# PCB_CREATING.net
KiCad netlist of a schematic drawn in EasyEDA
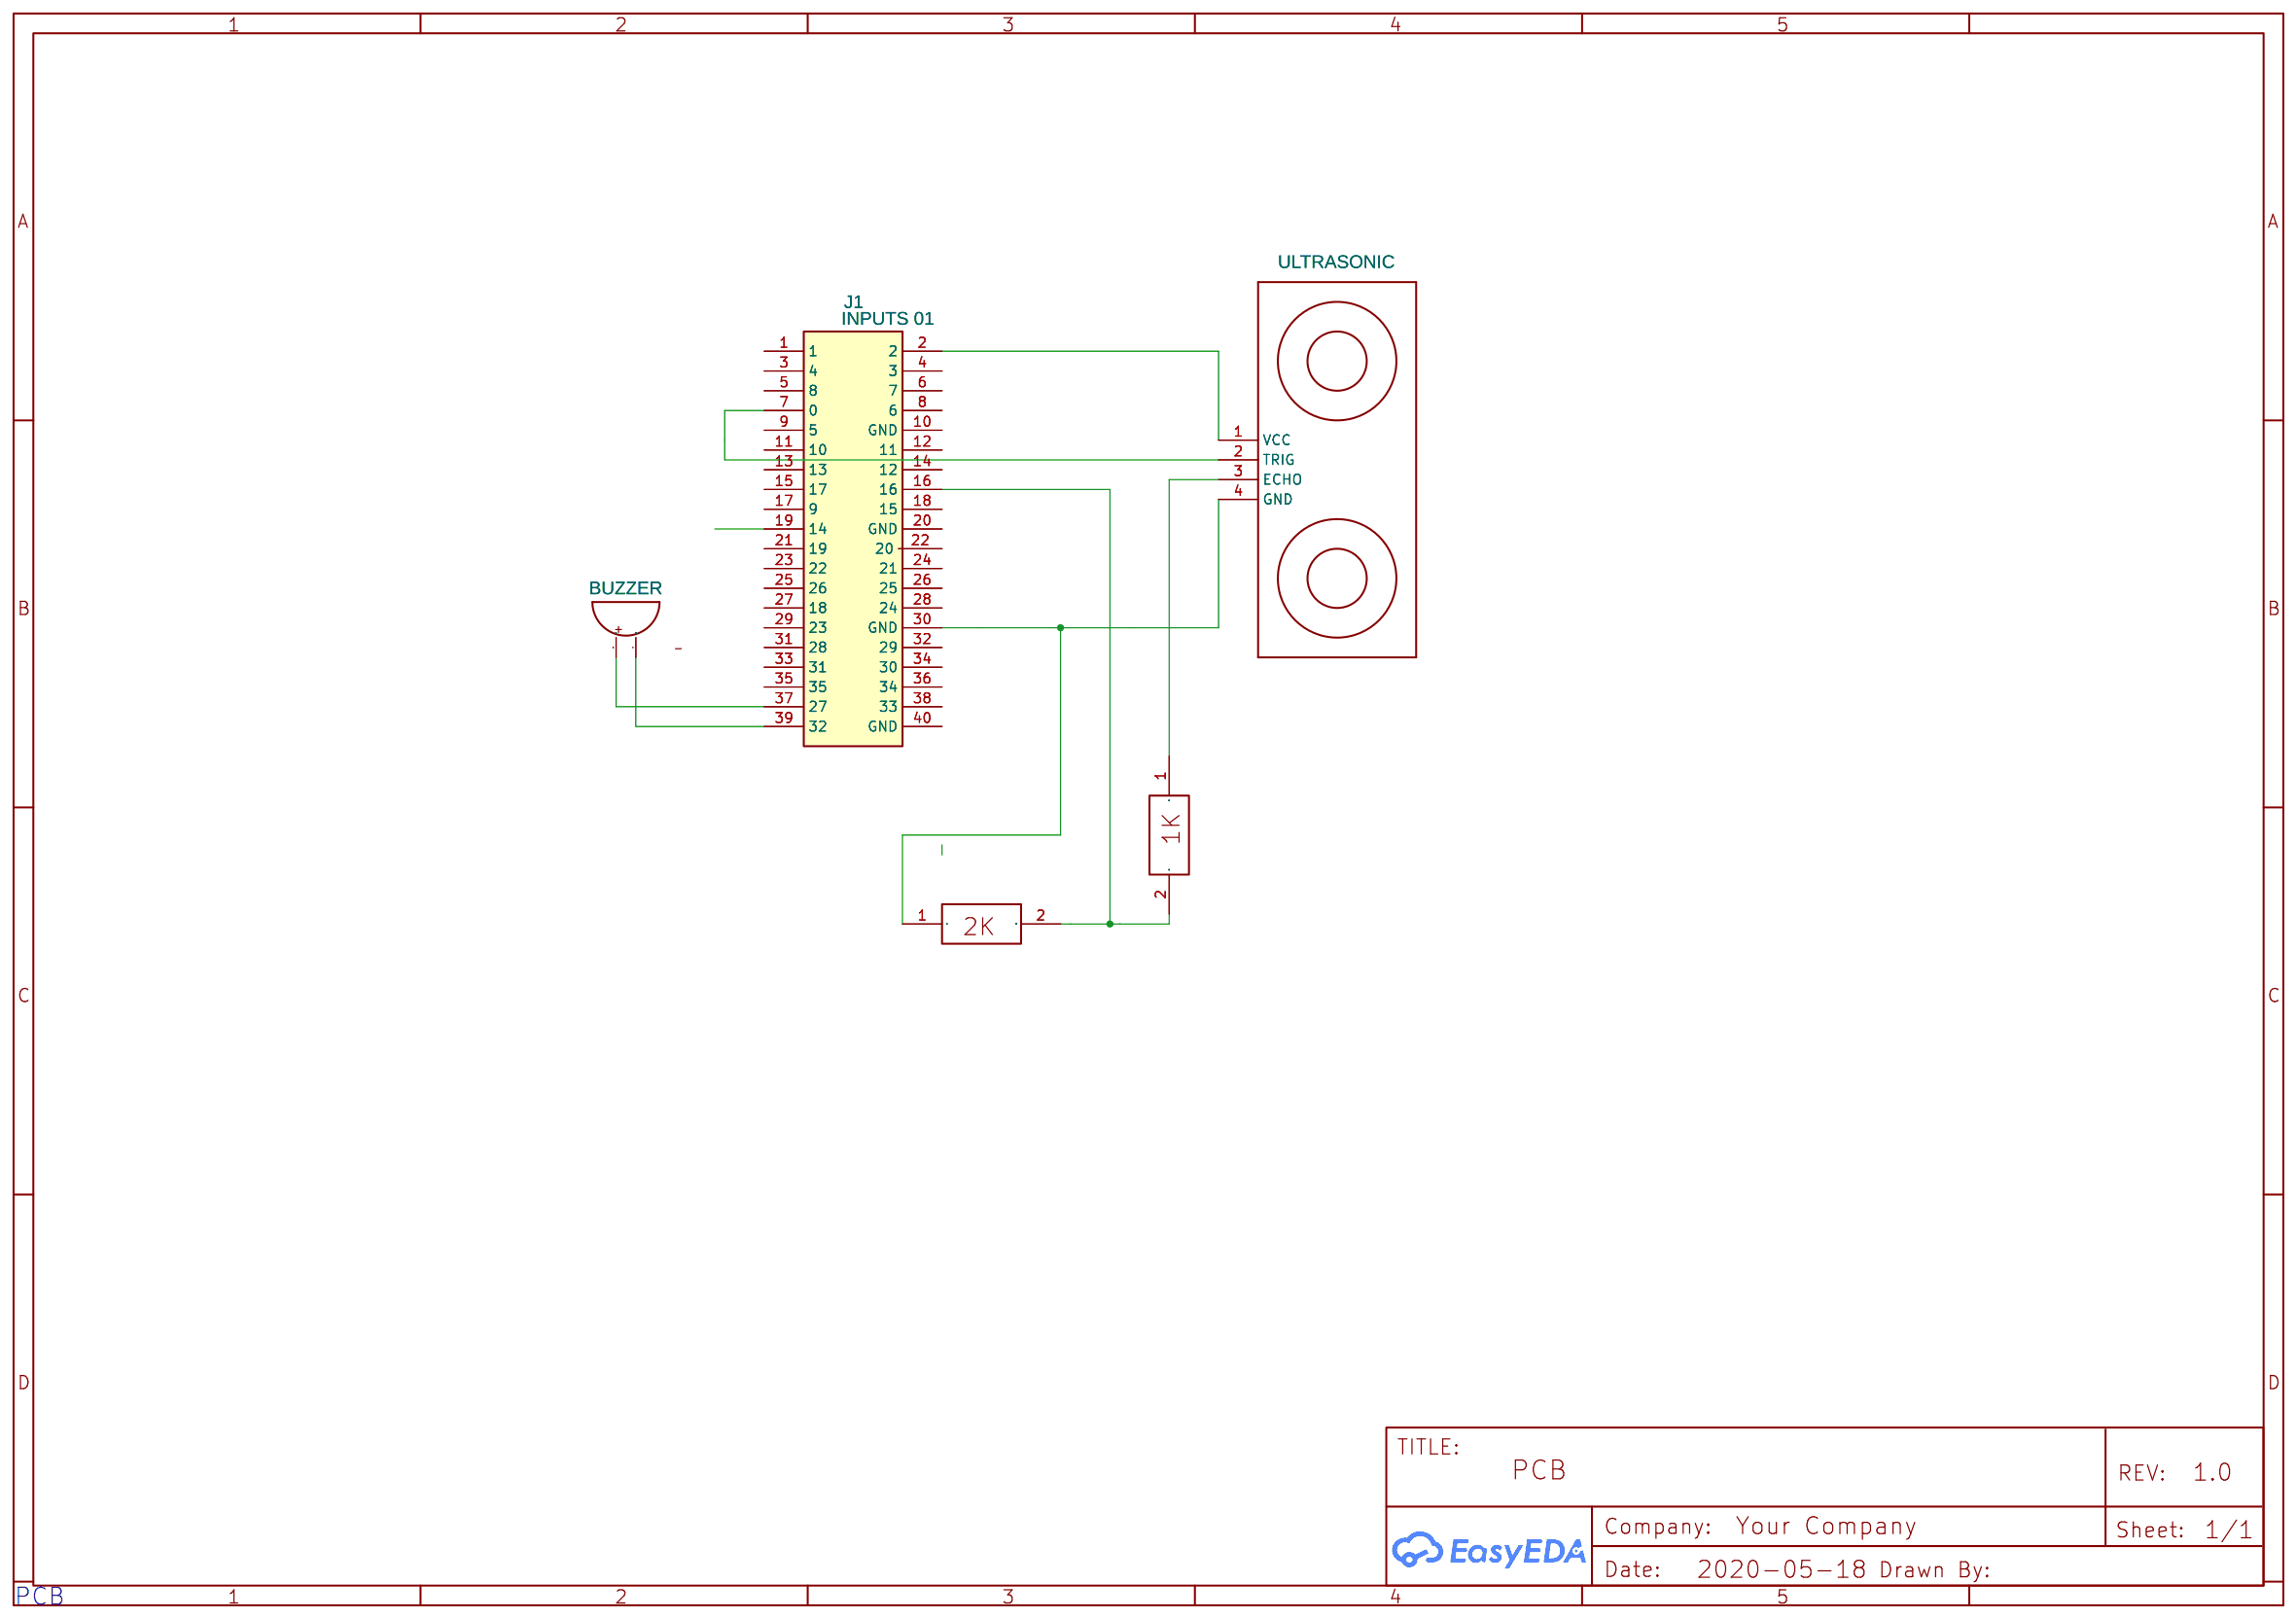
[diagram p0: schematic sheet]

(export (version "E")
  (design (tool "Eeschema 10.0.6"))
  (components
    (comp (ref "J1")
      (value "INPUTS 01")
      (fields
        (field (name "BOM_Manufacturer Part") "Header-Female-2.54_2x20")
        (field (name "BOM_Supplier Part") "C30420")
      )
      (libsource (lib "") (part "INPUTS 01"))
    )
    (comp (ref "R1") (value "1K resistor") (libsource (lib "") (part "1K resistor_1")))
    (comp (ref "R2") (value "1K resistor") (libsource (lib "") (part "1K resistor")))
    (comp (ref "SG1") (value "BUZZER") (libsource (lib "") (part "BUZZER")))
    (comp (ref "U1") (value "ULTRASONIC") (libsource (lib "") (part "ULTRASONIC")))
  )
  (nets
    (net (code "1") (name "Net-(J1-0)") (class "Default")
      (node (ref "J1") (pin "7") (pinfunction "0_7") (pintype "input"))
      (node (ref "U1") (pin "2") (pinfunction "TRIG_2") (pintype "input"))
    )
    (net (code "2") (name "Net-(J1-27)") (class "Default")
      (node (ref "J1") (pin "37") (pinfunction "27_37") (pintype "input"))
      (node (ref "SG1") (pin "+") (pinfunction "1_+") (pintype "unspecified"))
    )
    (net (code "3") (name "Net-(J1-32)") (class "Default")
      (node (ref "J1") (pin "39") (pinfunction "32_39") (pintype "input"))
      (node (ref "SG1") (pin "-") (pinfunction "2_-") (pintype "unspecified"))
    )
    (net (code "4") (name "Net-(J1-Pad16)") (class "Default")
      (node (ref "J1") (pin "16") (pinfunction "16_16") (pintype "input"))
      (node (ref "R1") (pin "2") (pinfunction "2_2") (pintype "unspecified"))
      (node (ref "R2") (pin "2") (pinfunction "2_2") (pintype "unspecified"))
    )
    (net (code "5") (name "Net-(U1-ECHO)") (class "Default")
      (node (ref "R1") (pin "1") (pinfunction "1_1") (pintype "unspecified"))
      (node (ref "U1") (pin "3") (pinfunction "ECHO_3") (pintype "output"))
    )
    (net (code "6") (name "Net-(U1-GND)") (class "Default")
      (node (ref "J1") (pin "30") (pinfunction "GND_30") (pintype "input"))
      (node (ref "R2") (pin "1") (pinfunction "1_1") (pintype "unspecified"))
      (node (ref "U1") (pin "4") (pinfunction "GND_4") (pintype "passive"))
    )
    (net (code "7") (name "Net-(U1-VCC)") (class "Default")
      (node (ref "J1") (pin "2") (pinfunction "2_2") (pintype "input"))
      (node (ref "U1") (pin "1") (pinfunction "VCC_1") (pintype "passive"))
    )
    (net (code "8") (name "unconnected-(J1-3-Pad4)") (class "Default")
      (node (ref "J1") (pin "4") (pinfunction "3_4") (pintype "input"))
    )
    (net (code "9") (name "unconnected-(J1-4-Pad3)") (class "Default")
      (node (ref "J1") (pin "3") (pinfunction "4_3") (pintype "input"))
    )
    (net (code "10") (name "unconnected-(J1-5-Pad9)") (class "Default")
      (node (ref "J1") (pin "9") (pinfunction "5_9") (pintype "input"))
    )
    (net (code "11") (name "unconnected-(J1-6-Pad8)") (class "Default")
      (node (ref "J1") (pin "8") (pinfunction "6_8") (pintype "input"))
    )
    (net (code "12") (name "unconnected-(J1-7-Pad6)") (class "Default")
      (node (ref "J1") (pin "6") (pinfunction "7_6") (pintype "input"))
    )
    (net (code "13") (name "unconnected-(J1-8-Pad5)") (class "Default")
      (node (ref "J1") (pin "5") (pinfunction "8_5") (pintype "input"))
    )
    (net (code "14") (name "unconnected-(J1-9-Pad17)") (class "Default")
      (node (ref "J1") (pin "17") (pinfunction "9_17") (pintype "input"))
    )
    (net (code "15") (name "unconnected-(J1-10-Pad11)") (class "Default")
      (node (ref "J1") (pin "11") (pinfunction "10_11") (pintype "input"))
    )
    (net (code "16") (name "unconnected-(J1-11-Pad12)") (class "Default")
      (node (ref "J1") (pin "12") (pinfunction "11_12") (pintype "input"))
    )
    (net (code "17") (name "unconnected-(J1-12-Pad14)") (class "Default")
      (node (ref "J1") (pin "14") (pinfunction "12_14") (pintype "input"))
    )
    (net (code "18") (name "unconnected-(J1-14-Pad19)") (class "Default")
      (node (ref "J1") (pin "19") (pinfunction "14_19") (pintype "input"))
    )
    (net (code "19") (name "unconnected-(J1-15-Pad18)") (class "Default")
      (node (ref "J1") (pin "18") (pinfunction "15_18") (pintype "input"))
    )
    (net (code "20") (name "unconnected-(J1-17-Pad15)") (class "Default")
      (node (ref "J1") (pin "15") (pinfunction "17_15") (pintype "input"))
    )
    (net (code "21") (name "unconnected-(J1-18-Pad27)") (class "Default")
      (node (ref "J1") (pin "27") (pinfunction "18_27") (pintype "input"))
    )
    (net (code "22") (name "unconnected-(J1-19-Pad21)") (class "Default")
      (node (ref "J1") (pin "21") (pinfunction "19_21") (pintype "input"))
    )
    (net (code "23") (name "unconnected-(J1-20-Pad22)") (class "Default")
      (node (ref "J1") (pin "22") (pinfunction "20_22") (pintype "input"))
    )
    (net (code "24") (name "unconnected-(J1-21-Pad24)") (class "Default")
      (node (ref "J1") (pin "24") (pinfunction "21_24") (pintype "input"))
    )
    (net (code "25") (name "unconnected-(J1-22-Pad23)") (class "Default")
      (node (ref "J1") (pin "23") (pinfunction "22_23") (pintype "input"))
    )
    (net (code "26") (name "unconnected-(J1-23-Pad29)") (class "Default")
      (node (ref "J1") (pin "29") (pinfunction "23_29") (pintype "input"))
    )
    (net (code "27") (name "unconnected-(J1-24-Pad28)") (class "Default")
      (node (ref "J1") (pin "28") (pinfunction "24_28") (pintype "input"))
    )
    (net (code "28") (name "unconnected-(J1-25-Pad26)") (class "Default")
      (node (ref "J1") (pin "26") (pinfunction "25_26") (pintype "input"))
    )
    (net (code "29") (name "unconnected-(J1-26-Pad25)") (class "Default")
      (node (ref "J1") (pin "25") (pinfunction "26_25") (pintype "input"))
    )
    (net (code "30") (name "unconnected-(J1-28-Pad31)") (class "Default")
      (node (ref "J1") (pin "31") (pinfunction "28_31") (pintype "input"))
    )
    (net (code "31") (name "unconnected-(J1-29-Pad32)") (class "Default")
      (node (ref "J1") (pin "32") (pinfunction "29_32") (pintype "input"))
    )
    (net (code "32") (name "unconnected-(J1-30-Pad34)") (class "Default")
      (node (ref "J1") (pin "34") (pinfunction "30_34") (pintype "input"))
    )
    (net (code "33") (name "unconnected-(J1-31-Pad33)") (class "Default")
      (node (ref "J1") (pin "33") (pinfunction "31_33") (pintype "input"))
    )
    (net (code "34") (name "unconnected-(J1-33-Pad38)") (class "Default")
      (node (ref "J1") (pin "38") (pinfunction "33_38") (pintype "input"))
    )
    (net (code "35") (name "unconnected-(J1-34-Pad36)") (class "Default")
      (node (ref "J1") (pin "36") (pinfunction "34_36") (pintype "input"))
    )
    (net (code "36") (name "unconnected-(J1-GND-Pad10)") (class "Default")
      (node (ref "J1") (pin "10") (pinfunction "GND_10") (pintype "input"))
    )
    (net (code "37") (name "unconnected-(J1-GND-Pad20)") (class "Default")
      (node (ref "J1") (pin "20") (pinfunction "GND_20") (pintype "input"))
    )
    (net (code "38") (name "unconnected-(J1-GND-Pad40)") (class "Default")
      (node (ref "J1") (pin "40") (pinfunction "GND_40") (pintype "input"))
    )
    (net (code "39") (name "unconnected-(J1-Pad1)") (class "Default")
      (node (ref "J1") (pin "1") (pinfunction "1_1") (pintype "input"))
    )
    (net (code "40") (name "unconnected-(J1-Pad13)") (class "Default")
      (node (ref "J1") (pin "13") (pinfunction "13_13") (pintype "input"))
    )
    (net (code "41") (name "unconnected-(J1-Pad35)") (class "Default")
      (node (ref "J1") (pin "35") (pinfunction "35_35") (pintype "input"))
    )
  )
)
